# DB15M.net
KiCad netlist of a schematic drawn in Altium Designer
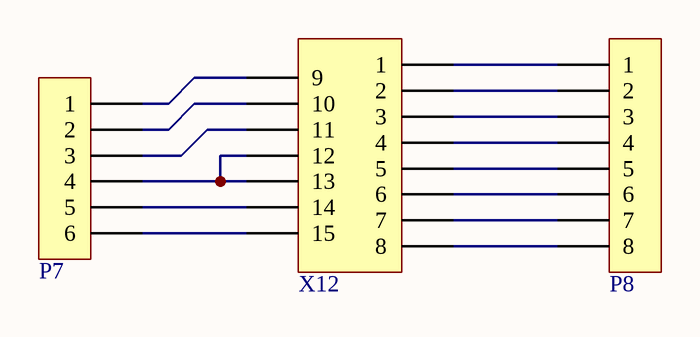
[diagram p0: DB15M.SchDoc]

(export (version "E")
  (design (tool "Eeschema 10.0.6"))
  (components
    (comp (ref "P7")
      (value "SIL-CONN-6")
      (footprint "SIL-CONN-6-R1")
      (libsource (lib "SchLib1") (part "SIL-CONN-6"))
    )
    (comp (ref "P8")
      (value "SIL-CONN-8")
      (footprint "SIL-CONN-8-R1")
      (libsource (lib "SchLib1") (part "SIL-CONN-8"))
    )
    (comp (ref "X12") (value "DB-15") (footprint "DB15M") (libsource (lib "SchLib1") (part "DB-15")))
  )
  (nets
    (net (code "1") (name "Net-(P7-Pad1)") (class "Default")
      (node (ref "P7") (pin "1") (pinfunction "1_1") (pintype "passive"))
      (node (ref "X12") (pin "9") (pinfunction "9_9") (pintype "passive"))
    )
    (net (code "2") (name "Net-(P7-Pad2)") (class "Default")
      (node (ref "P7") (pin "2") (pinfunction "2_2") (pintype "passive"))
      (node (ref "X12") (pin "10") (pinfunction "10_10") (pintype "passive"))
    )
    (net (code "3") (name "Net-(P7-Pad3)") (class "Default")
      (node (ref "P7") (pin "3") (pinfunction "3_3") (pintype "passive"))
      (node (ref "X12") (pin "11") (pinfunction "11_11") (pintype "passive"))
    )
    (net (code "4") (name "Net-(P7-Pad4)") (class "Default")
      (node (ref "P7") (pin "4") (pinfunction "4_4") (pintype "passive"))
      (node (ref "X12") (pin "12") (pinfunction "12_12") (pintype "passive"))
      (node (ref "X12") (pin "13") (pinfunction "13_13") (pintype "passive"))
    )
    (net (code "5") (name "Net-(P7-Pad5)") (class "Default")
      (node (ref "P7") (pin "5") (pinfunction "5_5") (pintype "passive"))
      (node (ref "X12") (pin "14") (pinfunction "14_14") (pintype "passive"))
    )
    (net (code "6") (name "Net-(P7-Pad6)") (class "Default")
      (node (ref "P7") (pin "6") (pinfunction "6_6") (pintype "passive"))
      (node (ref "X12") (pin "15") (pinfunction "15_15") (pintype "passive"))
    )
    (net (code "7") (name "Net-(P8-Pad1)") (class "Default")
      (node (ref "P8") (pin "1") (pinfunction "1_1") (pintype "passive"))
      (node (ref "X12") (pin "1") (pinfunction "1_1") (pintype "passive"))
    )
    (net (code "8") (name "Net-(P8-Pad2)") (class "Default")
      (node (ref "P8") (pin "2") (pinfunction "2_2") (pintype "passive"))
      (node (ref "X12") (pin "2") (pinfunction "2_2") (pintype "passive"))
    )
    (net (code "9") (name "Net-(P8-Pad3)") (class "Default")
      (node (ref "P8") (pin "3") (pinfunction "3_3") (pintype "passive"))
      (node (ref "X12") (pin "3") (pinfunction "3_3") (pintype "passive"))
    )
    (net (code "10") (name "Net-(P8-Pad4)") (class "Default")
      (node (ref "P8") (pin "4") (pinfunction "4_4") (pintype "passive"))
      (node (ref "X12") (pin "4") (pinfunction "4_4") (pintype "passive"))
    )
    (net (code "11") (name "Net-(P8-Pad5)") (class "Default")
      (node (ref "P8") (pin "5") (pinfunction "5_5") (pintype "passive"))
      (node (ref "X12") (pin "5") (pinfunction "5_5") (pintype "passive"))
    )
    (net (code "12") (name "Net-(P8-Pad6)") (class "Default")
      (node (ref "P8") (pin "6") (pinfunction "6_6") (pintype "passive"))
      (node (ref "X12") (pin "6") (pinfunction "6_6") (pintype "passive"))
    )
    (net (code "13") (name "Net-(P8-Pad7)") (class "Default")
      (node (ref "P8") (pin "7") (pinfunction "7_7") (pintype "passive"))
      (node (ref "X12") (pin "7") (pinfunction "7_7") (pintype "passive"))
    )
    (net (code "14") (name "Net-(P8-Pad8)") (class "Default")
      (node (ref "P8") (pin "8") (pinfunction "8_8") (pintype "passive"))
      (node (ref "X12") (pin "8") (pinfunction "8_8") (pintype "passive"))
    )
  )
)
